# Clock_Updated_3_Nets.net
KiCad netlist of a schematic drawn in EAGLE
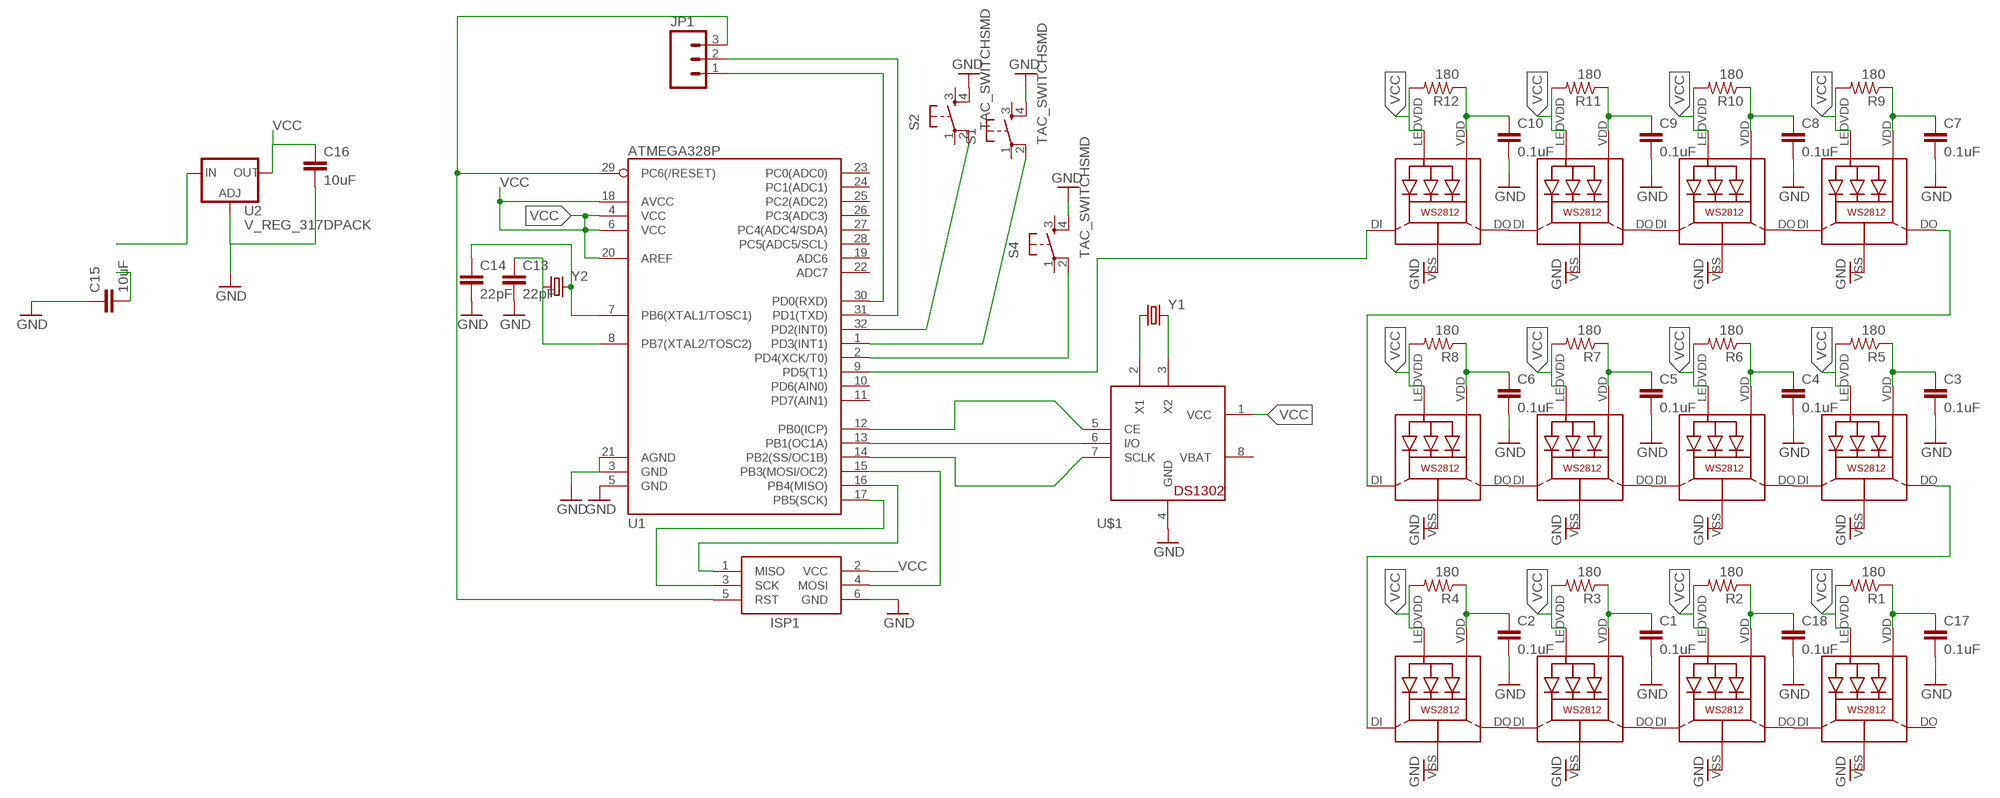
[diagram p0: schematic, sheet 1]

(export (version "E")
  (design (tool "Eeschema 10.0.6"))
  (components
    (comp (ref "C1")
      (value "0.1uF")
      (footprint "eagle-import:0603-CAP")
      (libsource (lib "eagle-import") (part "0.1UF-25V(+80/-20%)(0603)"))
    )
    (comp (ref "C2")
      (value "0.1uF")
      (footprint "eagle-import:0603-CAP")
      (libsource (lib "eagle-import") (part "0.1UF-25V(+80/-20%)(0603)"))
    )
    (comp (ref "C3")
      (value "0.1uF")
      (footprint "eagle-import:0603-CAP")
      (libsource (lib "eagle-import") (part "0.1UF-25V(+80/-20%)(0603)"))
    )
    (comp (ref "C4")
      (value "0.1uF")
      (footprint "eagle-import:0603-CAP")
      (libsource (lib "eagle-import") (part "0.1UF-25V(+80/-20%)(0603)"))
    )
    (comp (ref "C5")
      (value "0.1uF")
      (footprint "eagle-import:0603-CAP")
      (libsource (lib "eagle-import") (part "0.1UF-25V(+80/-20%)(0603)"))
    )
    (comp (ref "C6")
      (value "0.1uF")
      (footprint "eagle-import:0603-CAP")
      (libsource (lib "eagle-import") (part "0.1UF-25V(+80/-20%)(0603)"))
    )
    (comp (ref "C7")
      (value "0.1uF")
      (footprint "eagle-import:0603-CAP")
      (libsource (lib "eagle-import") (part "0.1UF-25V(+80/-20%)(0603)"))
    )
    (comp (ref "C8")
      (value "0.1uF")
      (footprint "eagle-import:0603-CAP")
      (libsource (lib "eagle-import") (part "0.1UF-25V(+80/-20%)(0603)"))
    )
    (comp (ref "C9")
      (value "0.1uF")
      (footprint "eagle-import:0603-CAP")
      (libsource (lib "eagle-import") (part "0.1UF-25V(+80/-20%)(0603)"))
    )
    (comp (ref "C10")
      (value "0.1uF")
      (footprint "eagle-import:0603-CAP")
      (libsource (lib "eagle-import") (part "0.1UF-25V(+80/-20%)(0603)"))
    )
    (comp (ref "C13")
      (value "22pF")
      (footprint "eagle-import:0603-CAP")
      (libsource (lib "eagle-import") (part "22PF-50V-5%(0603)"))
    )
    (comp (ref "C14")
      (value "22pF")
      (footprint "eagle-import:0603-CAP")
      (libsource (lib "eagle-import") (part "22PF-50V-5%(0603)"))
    )
    (comp (ref "C15")
      (value "10uF")
      (footprint "eagle-import:1206")
      (libsource (lib "eagle-import") (part "10UF-6.3V-20%(1206)"))
    )
    (comp (ref "C16")
      (value "10uF")
      (footprint "eagle-import:1206")
      (libsource (lib "eagle-import") (part "10UF-6.3V-20%(1206)"))
    )
    (comp (ref "C17")
      (value "0.1uF")
      (footprint "eagle-import:0603-CAP")
      (libsource (lib "eagle-import") (part "0.1UF-25V(+80/-20%)(0603)"))
    )
    (comp (ref "C18")
      (value "0.1uF")
      (footprint "eagle-import:0603-CAP")
      (libsource (lib "eagle-import") (part "0.1UF-25V(+80/-20%)(0603)"))
    )
    (comp (ref "ISP1")
      (value "AVRISP-6")
      (footprint "eagle-import:AVRISP")
      (libsource (lib "eagle-import") (part "AVRISP-6"))
    )
    (comp (ref "JP1")
      (value "M03JST-PTH-VERT")
      (footprint "eagle-import:JST-3-PTH-VERT")
      (libsource (lib "eagle-import") (part "M03JST-PTH-VERT"))
    )
    (comp (ref "LED1")
      (value "WS2812")
      (footprint "eagle-import:WS2812")
      (libsource (lib "eagle-import") (part "WS2812"))
    )
    (comp (ref "LED2")
      (value "WS2812")
      (footprint "eagle-import:WS2812")
      (libsource (lib "eagle-import") (part "WS2812"))
    )
    (comp (ref "LED3")
      (value "WS2812")
      (footprint "eagle-import:WS2812")
      (libsource (lib "eagle-import") (part "WS2812"))
    )
    (comp (ref "LED4")
      (value "WS2812")
      (footprint "eagle-import:WS2812")
      (libsource (lib "eagle-import") (part "WS2812"))
    )
    (comp (ref "LED5")
      (value "WS2812")
      (footprint "eagle-import:WS2812")
      (libsource (lib "eagle-import") (part "WS2812"))
    )
    (comp (ref "LED6")
      (value "WS2812")
      (footprint "eagle-import:WS2812")
      (libsource (lib "eagle-import") (part "WS2812"))
    )
    (comp (ref "LED7")
      (value "WS2812")
      (footprint "eagle-import:WS2812")
      (libsource (lib "eagle-import") (part "WS2812"))
    )
    (comp (ref "LED8")
      (value "WS2812")
      (footprint "eagle-import:WS2812")
      (libsource (lib "eagle-import") (part "WS2812"))
    )
    (comp (ref "LED9")
      (value "WS2812")
      (footprint "eagle-import:WS2812")
      (libsource (lib "eagle-import") (part "WS2812"))
    )
    (comp (ref "LED10")
      (value "WS2812")
      (footprint "eagle-import:WS2812")
      (libsource (lib "eagle-import") (part "WS2812"))
    )
    (comp (ref "LED13")
      (value "WS2812")
      (footprint "eagle-import:WS2812")
      (libsource (lib "eagle-import") (part "WS2812"))
    )
    (comp (ref "LED14")
      (value "WS2812")
      (footprint "eagle-import:WS2812")
      (libsource (lib "eagle-import") (part "WS2812"))
    )
    (comp (ref "R1")
      (value "180")
      (footprint "eagle-import:0603-RES")
      (libsource (lib "eagle-import") (part "180OHM1/10W1%(0603)"))
    )
    (comp (ref "R2")
      (value "180")
      (footprint "eagle-import:0603-RES")
      (libsource (lib "eagle-import") (part "180OHM1/10W1%(0603)"))
    )
    (comp (ref "R3")
      (value "180")
      (footprint "eagle-import:0603-RES")
      (libsource (lib "eagle-import") (part "180OHM1/10W1%(0603)"))
    )
    (comp (ref "R4")
      (value "180")
      (footprint "eagle-import:0603-RES")
      (libsource (lib "eagle-import") (part "180OHM1/10W1%(0603)"))
    )
    (comp (ref "R5")
      (value "180")
      (footprint "eagle-import:0603-RES")
      (libsource (lib "eagle-import") (part "180OHM1/10W1%(0603)"))
    )
    (comp (ref "R6")
      (value "180")
      (footprint "eagle-import:0603-RES")
      (libsource (lib "eagle-import") (part "180OHM1/10W1%(0603)"))
    )
    (comp (ref "R7")
      (value "180")
      (footprint "eagle-import:0603-RES")
      (libsource (lib "eagle-import") (part "180OHM1/10W1%(0603)"))
    )
    (comp (ref "R8")
      (value "180")
      (footprint "eagle-import:0603-RES")
      (libsource (lib "eagle-import") (part "180OHM1/10W1%(0603)"))
    )
    (comp (ref "R9")
      (value "180")
      (footprint "eagle-import:0603-RES")
      (libsource (lib "eagle-import") (part "180OHM1/10W1%(0603)"))
    )
    (comp (ref "R10")
      (value "180")
      (footprint "eagle-import:0603-RES")
      (libsource (lib "eagle-import") (part "180OHM1/10W1%(0603)"))
    )
    (comp (ref "R11")
      (value "180")
      (footprint "eagle-import:0603-RES")
      (libsource (lib "eagle-import") (part "180OHM1/10W1%(0603)"))
    )
    (comp (ref "R12")
      (value "180")
      (footprint "eagle-import:0603-RES")
      (libsource (lib "eagle-import") (part "180OHM1/10W1%(0603)"))
    )
    (comp (ref "S1")
      (value "TAC_SWITCHSMD")
      (footprint "eagle-import:TACTILE-SWITCH-SMD")
      (libsource (lib "eagle-import") (part "TAC_SWITCHSMD"))
    )
    (comp (ref "S2")
      (value "TAC_SWITCHSMD")
      (footprint "eagle-import:TACTILE-SWITCH-SMD")
      (libsource (lib "eagle-import") (part "TAC_SWITCHSMD"))
    )
    (comp (ref "S4")
      (value "TAC_SWITCHSMD")
      (footprint "eagle-import:TACTILE-SWITCH-SMD")
      (libsource (lib "eagle-import") (part "TAC_SWITCHSMD"))
    )
    (comp (ref "U$1")
      (value "DS1302")
      (footprint "eagle-import:DIL08-ROUND")
      (libsource (lib "eagle-import") (part "DS1302"))
    )
    (comp (ref "U1")
      (value "ATMEGA328P")
      (footprint "eagle-import:TQFP32-08")
      (libsource (lib "eagle-import") (part "ATMEGA328_SMT"))
    )
    (comp (ref "U2")
      (value "V_REG_317DPACK")
      (footprint "eagle-import:V-REG_DPACK")
      (libsource (lib "eagle-import") (part "V_REG_317DPACK"))
    )
    (comp (ref "Y1")
      (value "CRYSTALTC38H")
      (footprint "eagle-import:TC38H")
      (libsource (lib "eagle-import") (part "CRYSTALTC38H"))
    )
    (comp (ref "Y2")
      (value "CRYSTALSMD")
      (footprint "eagle-import:HC49UP")
      (libsource (lib "eagle-import") (part "CRYSTALSMD"))
    )
  )
  (nets
    (net (code "1") (name "/VBAT") (class "Default")
      (node (ref "U$1") (pin "8") (pinfunction "VBAT_8") (pintype "power_in"))
    )
    (net (code "2") (name "GND") (class "Default")
      (node (ref "C1") (pin "2") (pinfunction "2_2") (pintype "passive"))
      (node (ref "C10") (pin "2") (pinfunction "2_2") (pintype "passive"))
      (node (ref "C13") (pin "2") (pinfunction "2_2") (pintype "passive"))
      (node (ref "C14") (pin "2") (pinfunction "2_2") (pintype "passive"))
      (node (ref "C15") (pin "1") (pinfunction "1_1") (pintype "passive"))
      (node (ref "C16") (pin "2") (pinfunction "2_2") (pintype "passive"))
      (node (ref "C17") (pin "2") (pinfunction "2_2") (pintype "passive"))
      (node (ref "C18") (pin "2") (pinfunction "2_2") (pintype "passive"))
      (node (ref "C2") (pin "2") (pinfunction "2_2") (pintype "passive"))
      (node (ref "C3") (pin "2") (pinfunction "2_2") (pintype "passive"))
      (node (ref "C4") (pin "2") (pinfunction "2_2") (pintype "passive"))
      (node (ref "C5") (pin "2") (pinfunction "2_2") (pintype "passive"))
      (node (ref "C6") (pin "2") (pinfunction "2_2") (pintype "passive"))
      (node (ref "C7") (pin "2") (pinfunction "2_2") (pintype "passive"))
      (node (ref "C8") (pin "2") (pinfunction "2_2") (pintype "passive"))
      (node (ref "C9") (pin "2") (pinfunction "2_2") (pintype "passive"))
      (node (ref "ISP1") (pin "6") (pinfunction "GND_6") (pintype "power_in"))
      (node (ref "LED1") (pin "VSS") (pinfunction "GND_VSS") (pintype "power_in"))
      (node (ref "LED10") (pin "VSS") (pinfunction "GND_VSS") (pintype "power_in"))
      (node (ref "LED13") (pin "VSS") (pinfunction "GND_VSS") (pintype "power_in"))
      (node (ref "LED14") (pin "VSS") (pinfunction "GND_VSS") (pintype "power_in"))
      (node (ref "LED2") (pin "VSS") (pinfunction "GND_VSS") (pintype "power_in"))
      (node (ref "LED3") (pin "VSS") (pinfunction "GND_VSS") (pintype "power_in"))
      (node (ref "LED4") (pin "VSS") (pinfunction "GND_VSS") (pintype "power_in"))
      (node (ref "LED5") (pin "VSS") (pinfunction "GND_VSS") (pintype "power_in"))
      (node (ref "LED6") (pin "VSS") (pinfunction "GND_VSS") (pintype "power_in"))
      (node (ref "LED7") (pin "VSS") (pinfunction "GND_VSS") (pintype "power_in"))
      (node (ref "LED8") (pin "VSS") (pinfunction "GND_VSS") (pintype "power_in"))
      (node (ref "LED9") (pin "VSS") (pinfunction "GND_VSS") (pintype "power_in"))
      (node (ref "S1") (pin "4") (pinfunction "4_4") (pintype "passive"))
      (node (ref "S2") (pin "4") (pinfunction "4_4") (pintype "passive"))
      (node (ref "S4") (pin "4") (pinfunction "4_4") (pintype "passive"))
      (node (ref "U$1") (pin "4") (pinfunction "GND_4") (pintype "power_in"))
      (node (ref "U1") (pin "21") (pinfunction "AGND_21") (pintype "bidirectional"))
      (node (ref "U1") (pin "3") (pinfunction "GND_3") (pintype "bidirectional"))
      (node (ref "U1") (pin "5") (pinfunction "GND_5") (pintype "bidirectional"))
      (node (ref "U2") (pin "1") (pinfunction "ADJ_1") (pintype "input"))
    )
    (net (code "3") (name "Net-(C1-Pad1)") (class "Default")
      (node (ref "C1") (pin "1") (pinfunction "1_1") (pintype "passive"))
      (node (ref "LED1") (pin "VDD") (pinfunction "VDD_VDD") (pintype "power_in"))
      (node (ref "R3") (pin "1") (pinfunction "1_1") (pintype "passive"))
    )
    (net (code "4") (name "Net-(C2-Pad1)") (class "Default")
      (node (ref "C2") (pin "1") (pinfunction "1_1") (pintype "passive"))
      (node (ref "LED2") (pin "VDD") (pinfunction "VDD_VDD") (pintype "power_in"))
      (node (ref "R4") (pin "1") (pinfunction "1_1") (pintype "passive"))
    )
    (net (code "5") (name "Net-(C3-Pad1)") (class "Default")
      (node (ref "C3") (pin "1") (pinfunction "1_1") (pintype "passive"))
      (node (ref "LED3") (pin "VDD") (pinfunction "VDD_VDD") (pintype "power_in"))
      (node (ref "R5") (pin "1") (pinfunction "1_1") (pintype "passive"))
    )
    (net (code "6") (name "Net-(C4-Pad1)") (class "Default")
      (node (ref "C4") (pin "1") (pinfunction "1_1") (pintype "passive"))
      (node (ref "LED4") (pin "VDD") (pinfunction "VDD_VDD") (pintype "power_in"))
      (node (ref "R6") (pin "1") (pinfunction "1_1") (pintype "passive"))
    )
    (net (code "7") (name "Net-(C5-Pad1)") (class "Default")
      (node (ref "C5") (pin "1") (pinfunction "1_1") (pintype "passive"))
      (node (ref "LED5") (pin "VDD") (pinfunction "VDD_VDD") (pintype "power_in"))
      (node (ref "R7") (pin "1") (pinfunction "1_1") (pintype "passive"))
    )
    (net (code "8") (name "Net-(C6-Pad1)") (class "Default")
      (node (ref "C6") (pin "1") (pinfunction "1_1") (pintype "passive"))
      (node (ref "LED6") (pin "VDD") (pinfunction "VDD_VDD") (pintype "power_in"))
      (node (ref "R8") (pin "1") (pinfunction "1_1") (pintype "passive"))
    )
    (net (code "9") (name "Net-(C7-Pad1)") (class "Default")
      (node (ref "C7") (pin "1") (pinfunction "1_1") (pintype "passive"))
      (node (ref "LED7") (pin "VDD") (pinfunction "VDD_VDD") (pintype "power_in"))
      (node (ref "R9") (pin "1") (pinfunction "1_1") (pintype "passive"))
    )
    (net (code "10") (name "Net-(C8-Pad1)") (class "Default")
      (node (ref "C8") (pin "1") (pinfunction "1_1") (pintype "passive"))
      (node (ref "LED8") (pin "VDD") (pinfunction "VDD_VDD") (pintype "power_in"))
      (node (ref "R10") (pin "1") (pinfunction "1_1") (pintype "passive"))
    )
    (net (code "11") (name "Net-(C9-Pad1)") (class "Default")
      (node (ref "C9") (pin "1") (pinfunction "1_1") (pintype "passive"))
      (node (ref "LED9") (pin "VDD") (pinfunction "VDD_VDD") (pintype "power_in"))
      (node (ref "R11") (pin "1") (pinfunction "1_1") (pintype "passive"))
    )
    (net (code "12") (name "Net-(C10-Pad1)") (class "Default")
      (node (ref "C10") (pin "1") (pinfunction "1_1") (pintype "passive"))
      (node (ref "LED10") (pin "VDD") (pinfunction "VDD_VDD") (pintype "power_in"))
      (node (ref "R12") (pin "1") (pinfunction "1_1") (pintype "passive"))
    )
    (net (code "13") (name "Net-(C17-Pad1)") (class "Default")
      (node (ref "C17") (pin "1") (pinfunction "1_1") (pintype "passive"))
      (node (ref "LED13") (pin "VDD") (pinfunction "VDD_VDD") (pintype "power_in"))
      (node (ref "R1") (pin "1") (pinfunction "1_1") (pintype "passive"))
    )
    (net (code "14") (name "Net-(C18-Pad1)") (class "Default")
      (node (ref "C18") (pin "1") (pinfunction "1_1") (pintype "passive"))
      (node (ref "LED14") (pin "VDD") (pinfunction "VDD_VDD") (pintype "power_in"))
      (node (ref "R2") (pin "1") (pinfunction "1_1") (pintype "passive"))
    )
    (net (code "15") (name "Net-(ISP1-MISO)") (class "Default")
      (node (ref "ISP1") (pin "1") (pinfunction "MISO_1") (pintype "input"))
      (node (ref "U1") (pin "16") (pinfunction "PB4(MISO)_16") (pintype "bidirectional"))
    )
    (net (code "16") (name "Net-(ISP1-MOSI)") (class "Default")
      (node (ref "ISP1") (pin "4") (pinfunction "MOSI_4") (pintype "output"))
      (node (ref "U1") (pin "15") (pinfunction "PB3(MOSI/OC2)_15") (pintype "bidirectional"))
    )
    (net (code "17") (name "Net-(ISP1-RST)") (class "Default")
      (node (ref "ISP1") (pin "5") (pinfunction "RST_5") (pintype "output"))
      (node (ref "JP1") (pin "3") (pinfunction "3_3") (pintype "passive"))
      (node (ref "U1") (pin "29") (pinfunction "PC6(/RESET)_29") (pintype "bidirectional"))
    )
    (net (code "18") (name "Net-(ISP1-SCK)") (class "Default")
      (node (ref "ISP1") (pin "3") (pinfunction "SCK_3") (pintype "output"))
      (node (ref "U1") (pin "17") (pinfunction "PB5(SCK)_17") (pintype "bidirectional"))
    )
    (net (code "19") (name "Net-(LED1-PadDI)") (class "Default")
      (node (ref "LED1") (pin "DI") (pinfunction "DI_DI") (pintype "input"))
      (node (ref "LED2") (pin "DO") (pinfunction "DO_DO") (pintype "output"))
    )
    (net (code "20") (name "Net-(LED1-PadDO)") (class "Default")
      (node (ref "LED1") (pin "DO") (pinfunction "DO_DO") (pintype "output"))
      (node (ref "LED14") (pin "DI") (pinfunction "DI_DI") (pintype "input"))
    )
    (net (code "21") (name "Net-(LED1-PadLEDVDD)") (class "Default")
      (node (ref "LED1") (pin "LEDVDD") (pinfunction "LEDVDD_LEDVDD") (pintype "power_in"))
      (node (ref "R3") (pin "2") (pinfunction "2_2") (pintype "passive"))
    )
    (net (code "22") (name "Net-(LED2-PadDI)") (class "Default")
      (node (ref "LED2") (pin "DI") (pinfunction "DI_DI") (pintype "input"))
      (node (ref "LED3") (pin "DO") (pinfunction "DO_DO") (pintype "output"))
    )
    (net (code "23") (name "Net-(LED2-PadLEDVDD)") (class "Default")
      (node (ref "LED2") (pin "LEDVDD") (pinfunction "LEDVDD_LEDVDD") (pintype "power_in"))
      (node (ref "R4") (pin "2") (pinfunction "2_2") (pintype "passive"))
    )
    (net (code "24") (name "Net-(LED3-PadDI)") (class "Default")
      (node (ref "LED3") (pin "DI") (pinfunction "DI_DI") (pintype "input"))
      (node (ref "LED4") (pin "DO") (pinfunction "DO_DO") (pintype "output"))
    )
    (net (code "25") (name "Net-(LED3-PadLEDVDD)") (class "Default")
      (node (ref "LED3") (pin "LEDVDD") (pinfunction "LEDVDD_LEDVDD") (pintype "power_in"))
      (node (ref "R5") (pin "2") (pinfunction "2_2") (pintype "passive"))
    )
    (net (code "26") (name "Net-(LED4-PadDI)") (class "Default")
      (node (ref "LED4") (pin "DI") (pinfunction "DI_DI") (pintype "input"))
      (node (ref "LED5") (pin "DO") (pinfunction "DO_DO") (pintype "output"))
    )
    (net (code "27") (name "Net-(LED4-PadLEDVDD)") (class "Default")
      (node (ref "LED4") (pin "LEDVDD") (pinfunction "LEDVDD_LEDVDD") (pintype "power_in"))
      (node (ref "R6") (pin "2") (pinfunction "2_2") (pintype "passive"))
    )
    (net (code "28") (name "Net-(LED5-PadDI)") (class "Default")
      (node (ref "LED5") (pin "DI") (pinfunction "DI_DI") (pintype "input"))
      (node (ref "LED6") (pin "DO") (pinfunction "DO_DO") (pintype "output"))
    )
    (net (code "29") (name "Net-(LED5-PadLEDVDD)") (class "Default")
      (node (ref "LED5") (pin "LEDVDD") (pinfunction "LEDVDD_LEDVDD") (pintype "power_in"))
      (node (ref "R7") (pin "2") (pinfunction "2_2") (pintype "passive"))
    )
    (net (code "30") (name "Net-(LED6-PadDI)") (class "Default")
      (node (ref "LED6") (pin "DI") (pinfunction "DI_DI") (pintype "input"))
      (node (ref "LED7") (pin "DO") (pinfunction "DO_DO") (pintype "output"))
    )
    (net (code "31") (name "Net-(LED6-PadLEDVDD)") (class "Default")
      (node (ref "LED6") (pin "LEDVDD") (pinfunction "LEDVDD_LEDVDD") (pintype "power_in"))
      (node (ref "R8") (pin "2") (pinfunction "2_2") (pintype "passive"))
    )
    (net (code "32") (name "Net-(LED7-PadDI)") (class "Default")
      (node (ref "LED7") (pin "DI") (pinfunction "DI_DI") (pintype "input"))
      (node (ref "LED8") (pin "DO") (pinfunction "DO_DO") (pintype "output"))
    )
    (net (code "33") (name "Net-(LED7-PadLEDVDD)") (class "Default")
      (node (ref "LED7") (pin "LEDVDD") (pinfunction "LEDVDD_LEDVDD") (pintype "power_in"))
      (node (ref "R9") (pin "2") (pinfunction "2_2") (pintype "passive"))
    )
    (net (code "34") (name "Net-(LED8-PadDI)") (class "Default")
      (node (ref "LED8") (pin "DI") (pinfunction "DI_DI") (pintype "input"))
      (node (ref "LED9") (pin "DO") (pinfunction "DO_DO") (pintype "output"))
    )
    (net (code "35") (name "Net-(LED8-PadLEDVDD)") (class "Default")
      (node (ref "LED8") (pin "LEDVDD") (pinfunction "LEDVDD_LEDVDD") (pintype "power_in"))
      (node (ref "R10") (pin "2") (pinfunction "2_2") (pintype "passive"))
    )
    (net (code "36") (name "Net-(LED9-PadLEDVDD)") (class "Default")
      (node (ref "LED9") (pin "LEDVDD") (pinfunction "LEDVDD_LEDVDD") (pintype "power_in"))
      (node (ref "R11") (pin "2") (pinfunction "2_2") (pintype "passive"))
    )
    (net (code "37") (name "Net-(LED10-PadDO)") (class "Default")
      (node (ref "LED10") (pin "DO") (pinfunction "DO_DO") (pintype "output"))
      (node (ref "LED9") (pin "DI") (pinfunction "DI_DI") (pintype "input"))
    )
    (net (code "38") (name "Net-(LED10-PadLEDVDD)") (class "Default")
      (node (ref "LED10") (pin "LEDVDD") (pinfunction "LEDVDD_LEDVDD") (pintype "power_in"))
      (node (ref "R12") (pin "2") (pinfunction "2_2") (pintype "passive"))
    )
    (net (code "39") (name "Net-(LED13-PadDI)") (class "Default")
      (node (ref "LED13") (pin "DI") (pinfunction "DI_DI") (pintype "input"))
      (node (ref "LED14") (pin "DO") (pinfunction "DO_DO") (pintype "output"))
    )
    (net (code "40") (name "Net-(LED13-PadLEDVDD)") (class "Default")
      (node (ref "LED13") (pin "LEDVDD") (pinfunction "LEDVDD_LEDVDD") (pintype "power_in"))
      (node (ref "R1") (pin "2") (pinfunction "2_2") (pintype "passive"))
    )
    (net (code "41") (name "Net-(LED14-PadLEDVDD)") (class "Default")
      (node (ref "LED14") (pin "LEDVDD") (pinfunction "LEDVDD_LEDVDD") (pintype "power_in"))
      (node (ref "R2") (pin "2") (pinfunction "2_2") (pintype "passive"))
    )
    (net (code "42") (name "Net-(U$1-CE)") (class "Default")
      (node (ref "U$1") (pin "5") (pinfunction "CE_5") (pintype "input"))
      (node (ref "U1") (pin "12") (pinfunction "PB0(ICP)_12") (pintype "bidirectional"))
    )
    (net (code "43") (name "Net-(U$1-I{slash}O)") (class "Default")
      (node (ref "U$1") (pin "6") (pinfunction "I/O_6") (pintype "bidirectional"))
      (node (ref "U1") (pin "13") (pinfunction "PB1(OC1A)_13") (pintype "bidirectional"))
    )
    (net (code "44") (name "Net-(U$1-SCLK)") (class "Default")
      (node (ref "U$1") (pin "7") (pinfunction "SCLK_7") (pintype "input"))
      (node (ref "U1") (pin "14") (pinfunction "PB2(SS/OC1B)_14") (pintype "bidirectional"))
    )
    (net (code "45") (name "Net-(U$1-X1)") (class "Default")
      (node (ref "U$1") (pin "2") (pinfunction "X1_2") (pintype "passive"))
      (node (ref "Y1") (pin "1") (pinfunction "1_1") (pintype "passive"))
    )
    (net (code "46") (name "Net-(U$1-X2)") (class "Default")
      (node (ref "U$1") (pin "3") (pinfunction "X2_3") (pintype "passive"))
      (node (ref "Y1") (pin "2") (pinfunction "2_2") (pintype "passive"))
    )
    (net (code "47") (name "Net-(U1-PB6(XTAL1{slash}TOSC1))") (class "Default")
      (node (ref "C14") (pin "1") (pinfunction "1_1") (pintype "passive"))
      (node (ref "U1") (pin "7") (pinfunction "PB6(XTAL1/TOSC1)_7") (pintype "bidirectional"))
      (node (ref "Y2") (pin "2") (pinfunction "2_2") (pintype "passive"))
    )
    (net (code "48") (name "Net-(U1-PB7(XTAL2{slash}TOSC2))") (class "Default")
      (node (ref "C13") (pin "1") (pinfunction "1_1") (pintype "passive"))
      (node (ref "U1") (pin "8") (pinfunction "PB7(XTAL2/TOSC2)_8") (pintype "bidirectional"))
      (node (ref "Y2") (pin "1") (pinfunction "1_1") (pintype "passive"))
    )
    (net (code "49") (name "Net-(U1-PD0(RXD))") (class "Default")
      (node (ref "JP1") (pin "1") (pinfunction "1_1") (pintype "passive"))
      (node (ref "U1") (pin "30") (pinfunction "PD0(RXD)_30") (pintype "bidirectional"))
    )
    (net (code "50") (name "Net-(U1-PD1(TXD))") (class "Default")
      (node (ref "JP1") (pin "2") (pinfunction "2_2") (pintype "passive"))
      (node (ref "U1") (pin "31") (pinfunction "PD1(TXD)_31") (pintype "bidirectional"))
    )
    (net (code "51") (name "Net-(U1-PD2(INT0))") (class "Default")
      (node (ref "S2") (pin "2") (pinfunction "2_2") (pintype "passive"))
      (node (ref "U1") (pin "32") (pinfunction "PD2(INT0)_32") (pintype "bidirectional"))
    )
    (net (code "52") (name "Net-(U1-PD3(INT1))") (class "Default")
      (node (ref "S1") (pin "2") (pinfunction "2_2") (pintype "passive"))
      (node (ref "U1") (pin "1") (pinfunction "PD3(INT1)_1") (pintype "bidirectional"))
    )
    (net (code "53") (name "Net-(U1-PD4(XCK{slash}T0))") (class "Default")
      (node (ref "S4") (pin "2") (pinfunction "2_2") (pintype "passive"))
      (node (ref "U1") (pin "2") (pinfunction "PD4(XCK/T0)_2") (pintype "bidirectional"))
    )
    (net (code "54") (name "Net-(U1-PD5(T1))") (class "Default")
      (node (ref "LED10") (pin "DI") (pinfunction "DI_DI") (pintype "input"))
      (node (ref "U1") (pin "9") (pinfunction "PD5(T1)_9") (pintype "bidirectional"))
    )
    (net (code "55") (name "VCC") (class "Default")
      (node (ref "C16") (pin "1") (pinfunction "1_1") (pintype "passive"))
      (node (ref "ISP1") (pin "2") (pinfunction "VCC_2") (pintype "power_in"))
      (node (ref "U$1") (pin "1") (pinfunction "VCC_1") (pintype "power_in"))
      (node (ref "U1") (pin "18") (pinfunction "AVCC_18") (pintype "bidirectional"))
      (node (ref "U1") (pin "20") (pinfunction "AREF_20") (pintype "bidirectional"))
      (node (ref "U1") (pin "4") (pinfunction "VCC_4") (pintype "bidirectional"))
      (node (ref "U1") (pin "6") (pinfunction "VCC_6") (pintype "bidirectional"))
      (node (ref "U2") (pin "4") (pinfunction "OUT_4") (pintype "output"))
    )
    (net (code "56") (name "unconnected-(C15-Pad2)") (class "Default")
      (node (ref "C15") (pin "2") (pinfunction "2_2") (pintype "passive"))
    )
    (net (code "57") (name "unconnected-(LED13-PadDO)") (class "Default")
      (node (ref "LED13") (pin "DO") (pinfunction "DO_DO") (pintype "output"))
    )
    (net (code "58") (name "unconnected-(S1-Pad1)") (class "Default")
      (node (ref "S1") (pin "1") (pinfunction "1_1") (pintype "passive"))
    )
    (net (code "59") (name "unconnected-(S1-Pad3)") (class "Default")
      (node (ref "S1") (pin "3") (pinfunction "3_3") (pintype "passive"))
    )
    (net (code "60") (name "unconnected-(S2-Pad1)") (class "Default")
      (node (ref "S2") (pin "1") (pinfunction "1_1") (pintype "passive"))
    )
    (net (code "61") (name "unconnected-(S2-Pad3)") (class "Default")
      (node (ref "S2") (pin "3") (pinfunction "3_3") (pintype "passive"))
    )
    (net (code "62") (name "unconnected-(S4-Pad1)") (class "Default")
      (node (ref "S4") (pin "1") (pinfunction "1_1") (pintype "passive"))
    )
    (net (code "63") (name "unconnected-(S4-Pad3)") (class "Default")
      (node (ref "S4") (pin "3") (pinfunction "3_3") (pintype "passive"))
    )
    (net (code "64") (name "unconnected-(U1-ADC6-Pad19)") (class "Default")
      (node (ref "U1") (pin "19") (pinfunction "ADC6_19") (pintype "bidirectional"))
    )
    (net (code "65") (name "unconnected-(U1-ADC7-Pad22)") (class "Default")
      (node (ref "U1") (pin "22") (pinfunction "ADC7_22") (pintype "bidirectional"))
    )
    (net (code "66") (name "unconnected-(U1-PC0(ADC0)-Pad23)") (class "Default")
      (node (ref "U1") (pin "23") (pinfunction "PC0(ADC0)_23") (pintype "bidirectional"))
    )
    (net (code "67") (name "unconnected-(U1-PC1(ADC1)-Pad24)") (class "Default")
      (node (ref "U1") (pin "24") (pinfunction "PC1(ADC1)_24") (pintype "bidirectional"))
    )
    (net (code "68") (name "unconnected-(U1-PC2(ADC2)-Pad25)") (class "Default")
      (node (ref "U1") (pin "25") (pinfunction "PC2(ADC2)_25") (pintype "bidirectional"))
    )
    (net (code "69") (name "unconnected-(U1-PC3(ADC3)-Pad26)") (class "Default")
      (node (ref "U1") (pin "26") (pinfunction "PC3(ADC3)_26") (pintype "bidirectional"))
    )
    (net (code "70") (name "unconnected-(U1-PC4(ADC4{slash}SDA)-Pad27)") (class "Default")
      (node (ref "U1") (pin "27") (pinfunction "PC4(ADC4/SDA)_27") (pintype "bidirectional"))
    )
    (net (code "71") (name "unconnected-(U1-PC5(ADC5{slash}SCL)-Pad28)") (class "Default")
      (node (ref "U1") (pin "28") (pinfunction "PC5(ADC5/SCL)_28") (pintype "bidirectional"))
    )
    (net (code "72") (name "unconnected-(U1-PD6(AIN0)-Pad10)") (class "Default")
      (node (ref "U1") (pin "10") (pinfunction "PD6(AIN0)_10") (pintype "bidirectional"))
    )
    (net (code "73") (name "unconnected-(U1-PD7(AIN1)-Pad11)") (class "Default")
      (node (ref "U1") (pin "11") (pinfunction "PD7(AIN1)_11") (pintype "bidirectional"))
    )
    (net (code "74") (name "unconnected-(U2-IN-Pad3)") (class "Default")
      (node (ref "U2") (pin "3") (pinfunction "IN_3") (pintype "input"))
    )
  )
)
